# LK-1_Adapter.net
KiCad netlist of a schematic drawn in EAGLE
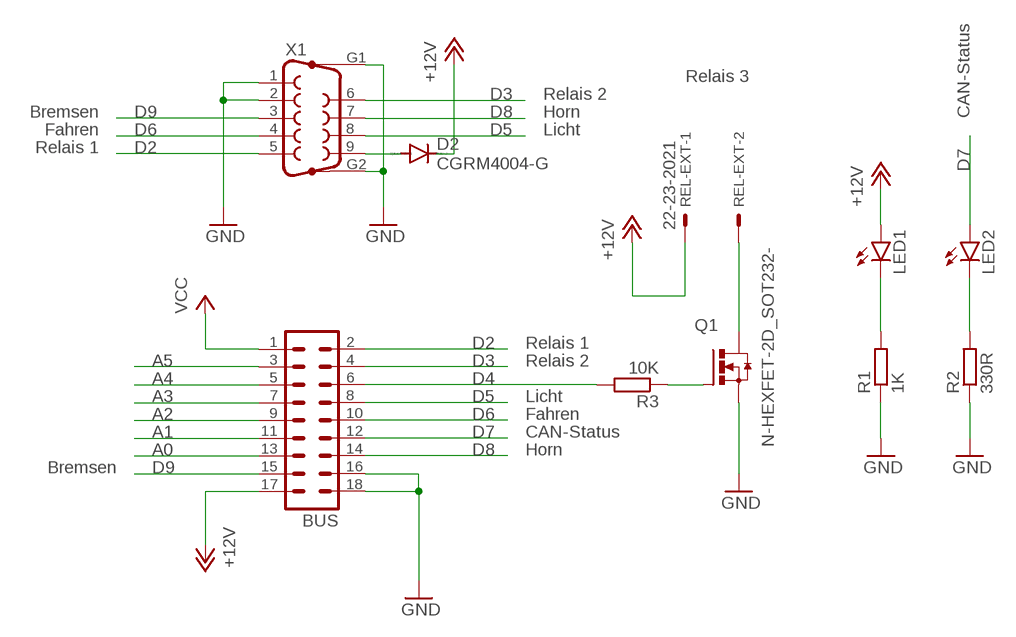
[diagram p0: schematic, sheet 1]

(export (version "E")
  (design (tool "Eeschema 10.0.6"))
  (components
    (comp (ref "BUS")
      (value "MA09-2")
      (footprint "eagle-import:MA09-2")
      (libsource (lib "eagle-import") (part "MA09-2"))
    )
    (comp (ref "D2")
      (value "CGRM4004-G")
      (footprint "eagle-import:SOD-123_MINI-SMA")
      (libsource (lib "eagle-import") (part "CGRM400-G4"))
    )
    (comp (ref "LED1")
      (value "LED3MM")
      (footprint "eagle-import:LED3MM")
      (libsource (lib "eagle-import") (part "LED3MM"))
    )
    (comp (ref "LED2")
      (value "LED3MM")
      (footprint "eagle-import:LED3MM")
      (libsource (lib "eagle-import") (part "LED3MM"))
    )
    (comp (ref "Q1")
      (value "N-HEXFET-2D_SOT232-")
      (footprint "eagle-import:SOT223")
      (libsource (lib "eagle-import") (part "N-HEXFET-2D_?-SOT232"))
    )
    (comp (ref "R1")
      (value "1K")
      (footprint "eagle-import:0204V")
      (libsource (lib "eagle-import") (part "R-EU_0204/2V"))
    )
    (comp (ref "R2")
      (value "330R")
      (footprint "eagle-import:0204V")
      (libsource (lib "eagle-import") (part "R-EU_0204/2V"))
    )
    (comp (ref "R3")
      (value "10K")
      (footprint "eagle-import:0204V")
      (libsource (lib "eagle-import") (part "R-EU_0204/2V"))
    )
    (comp (ref "REL-EXT")
      (value "22-23-2021")
      (footprint "eagle-import:22-23-2021")
      (fields (field (name "MF") "MOLEX"))
      (libsource (lib "eagle-import") (part "22-23-2021"))
    )
    (comp (ref "X1")
      (value "F09VP")
      (footprint "eagle-import:F09VP")
      (libsource (lib "eagle-import") (part "F09VP"))
    )
  )
  (nets
    (net (code "1") (name "+12V") (class "Default")
      (node (ref "BUS") (pin "17") (pinfunction "17_17") (pintype "passive"))
      (node (ref "D2") (pin "C") (pinfunction "C_C") (pintype "passive"))
      (node (ref "LED1") (pin "A") (pinfunction "A_A") (pintype "passive"))
      (node (ref "REL-EXT") (pin "1") (pinfunction "S_1") (pintype "passive"))
    )
    (net (code "2") (name "A0") (class "Default")
      (node (ref "BUS") (pin "13") (pinfunction "13_13") (pintype "passive"))
    )
    (net (code "3") (name "A1") (class "Default")
      (node (ref "BUS") (pin "11") (pinfunction "11_11") (pintype "passive"))
    )
    (net (code "4") (name "A2") (class "Default")
      (node (ref "BUS") (pin "9") (pinfunction "9_9") (pintype "passive"))
    )
    (net (code "5") (name "A3") (class "Default")
      (node (ref "BUS") (pin "7") (pinfunction "7_7") (pintype "passive"))
    )
    (net (code "6") (name "A4") (class "Default")
      (node (ref "BUS") (pin "5") (pinfunction "5_5") (pintype "passive"))
    )
    (net (code "7") (name "A5") (class "Default")
      (node (ref "BUS") (pin "3") (pinfunction "3_3") (pintype "passive"))
    )
    (net (code "8") (name "D2") (class "Default")
      (node (ref "BUS") (pin "2") (pinfunction "2_2") (pintype "passive"))
      (node (ref "X1") (pin "5") (pinfunction "5_5") (pintype "passive"))
    )
    (net (code "9") (name "D3") (class "Default")
      (node (ref "BUS") (pin "4") (pinfunction "4_4") (pintype "passive"))
      (node (ref "X1") (pin "6") (pinfunction "6_6") (pintype "passive"))
    )
    (net (code "10") (name "D4") (class "Default")
      (node (ref "BUS") (pin "6") (pinfunction "6_6") (pintype "passive"))
      (node (ref "R3") (pin "2") (pinfunction "2_2") (pintype "passive"))
    )
    (net (code "11") (name "D5") (class "Default")
      (node (ref "BUS") (pin "8") (pinfunction "8_8") (pintype "passive"))
      (node (ref "X1") (pin "8") (pinfunction "8_8") (pintype "passive"))
    )
    (net (code "12") (name "D6") (class "Default")
      (node (ref "BUS") (pin "10") (pinfunction "10_10") (pintype "passive"))
      (node (ref "X1") (pin "4") (pinfunction "4_4") (pintype "passive"))
    )
    (net (code "13") (name "D7") (class "Default")
      (node (ref "BUS") (pin "12") (pinfunction "12_12") (pintype "passive"))
      (node (ref "LED2") (pin "A") (pinfunction "A_A") (pintype "passive"))
    )
    (net (code "14") (name "D8") (class "Default")
      (node (ref "BUS") (pin "14") (pinfunction "14_14") (pintype "passive"))
      (node (ref "X1") (pin "7") (pinfunction "7_7") (pintype "passive"))
    )
    (net (code "15") (name "D9") (class "Default")
      (node (ref "BUS") (pin "15") (pinfunction "15_15") (pintype "passive"))
      (node (ref "X1") (pin "3") (pinfunction "3_3") (pintype "passive"))
    )
    (net (code "16") (name "GND") (class "Default")
      (node (ref "BUS") (pin "16") (pinfunction "16_16") (pintype "passive"))
      (node (ref "BUS") (pin "18") (pinfunction "18_18") (pintype "passive"))
      (node (ref "Q1") (pin "3") (pinfunction "S_3") (pintype "passive"))
      (node (ref "R1") (pin "1") (pinfunction "1_1") (pintype "passive"))
      (node (ref "R2") (pin "1") (pinfunction "1_1") (pintype "passive"))
      (node (ref "X1") (pin "1") (pinfunction "1_1") (pintype "passive"))
      (node (ref "X1") (pin "2") (pinfunction "2_2") (pintype "passive"))
      (node (ref "X1") (pin "G1") (pinfunction "G1_G1") (pintype "passive"))
      (node (ref "X1") (pin "G2") (pinfunction "G2_G2") (pintype "passive"))
    )
    (net (code "17") (name "Net-(D2-PadA)") (class "Default")
      (node (ref "D2") (pin "A") (pinfunction "A_A") (pintype "passive"))
      (node (ref "X1") (pin "9") (pinfunction "9_9") (pintype "passive"))
    )
    (net (code "18") (name "Net-(LED1-C)") (class "Default")
      (node (ref "LED1") (pin "K") (pinfunction "C_K") (pintype "passive"))
      (node (ref "R1") (pin "2") (pinfunction "2_2") (pintype "passive"))
    )
    (net (code "19") (name "Net-(LED2-C)") (class "Default")
      (node (ref "LED2") (pin "K") (pinfunction "C_K") (pintype "passive"))
      (node (ref "R2") (pin "2") (pinfunction "2_2") (pintype "passive"))
    )
    (net (code "20") (name "Net-(Q1-G)") (class "Default")
      (node (ref "Q1") (pin "1") (pinfunction "G_1") (pintype "passive"))
      (node (ref "R3") (pin "1") (pinfunction "1_1") (pintype "passive"))
    )
    (net (code "21") (name "Net-(REL-EXTB-S)") (class "Default")
      (node (ref "Q1") (pin "2") (pinfunction "D_2") (pintype "passive"))
      (node (ref "Q1") (pin "4") (pinfunction "D_4") (pintype "passive"))
      (node (ref "REL-EXT") (pin "2") (pinfunction "S_2") (pintype "passive"))
    )
    (net (code "22") (name "VCC") (class "Default")
      (node (ref "BUS") (pin "1") (pinfunction "1_1") (pintype "passive"))
    )
  )
)
